# pcb.net
KiCad netlist of a schematic drawn in EAGLE
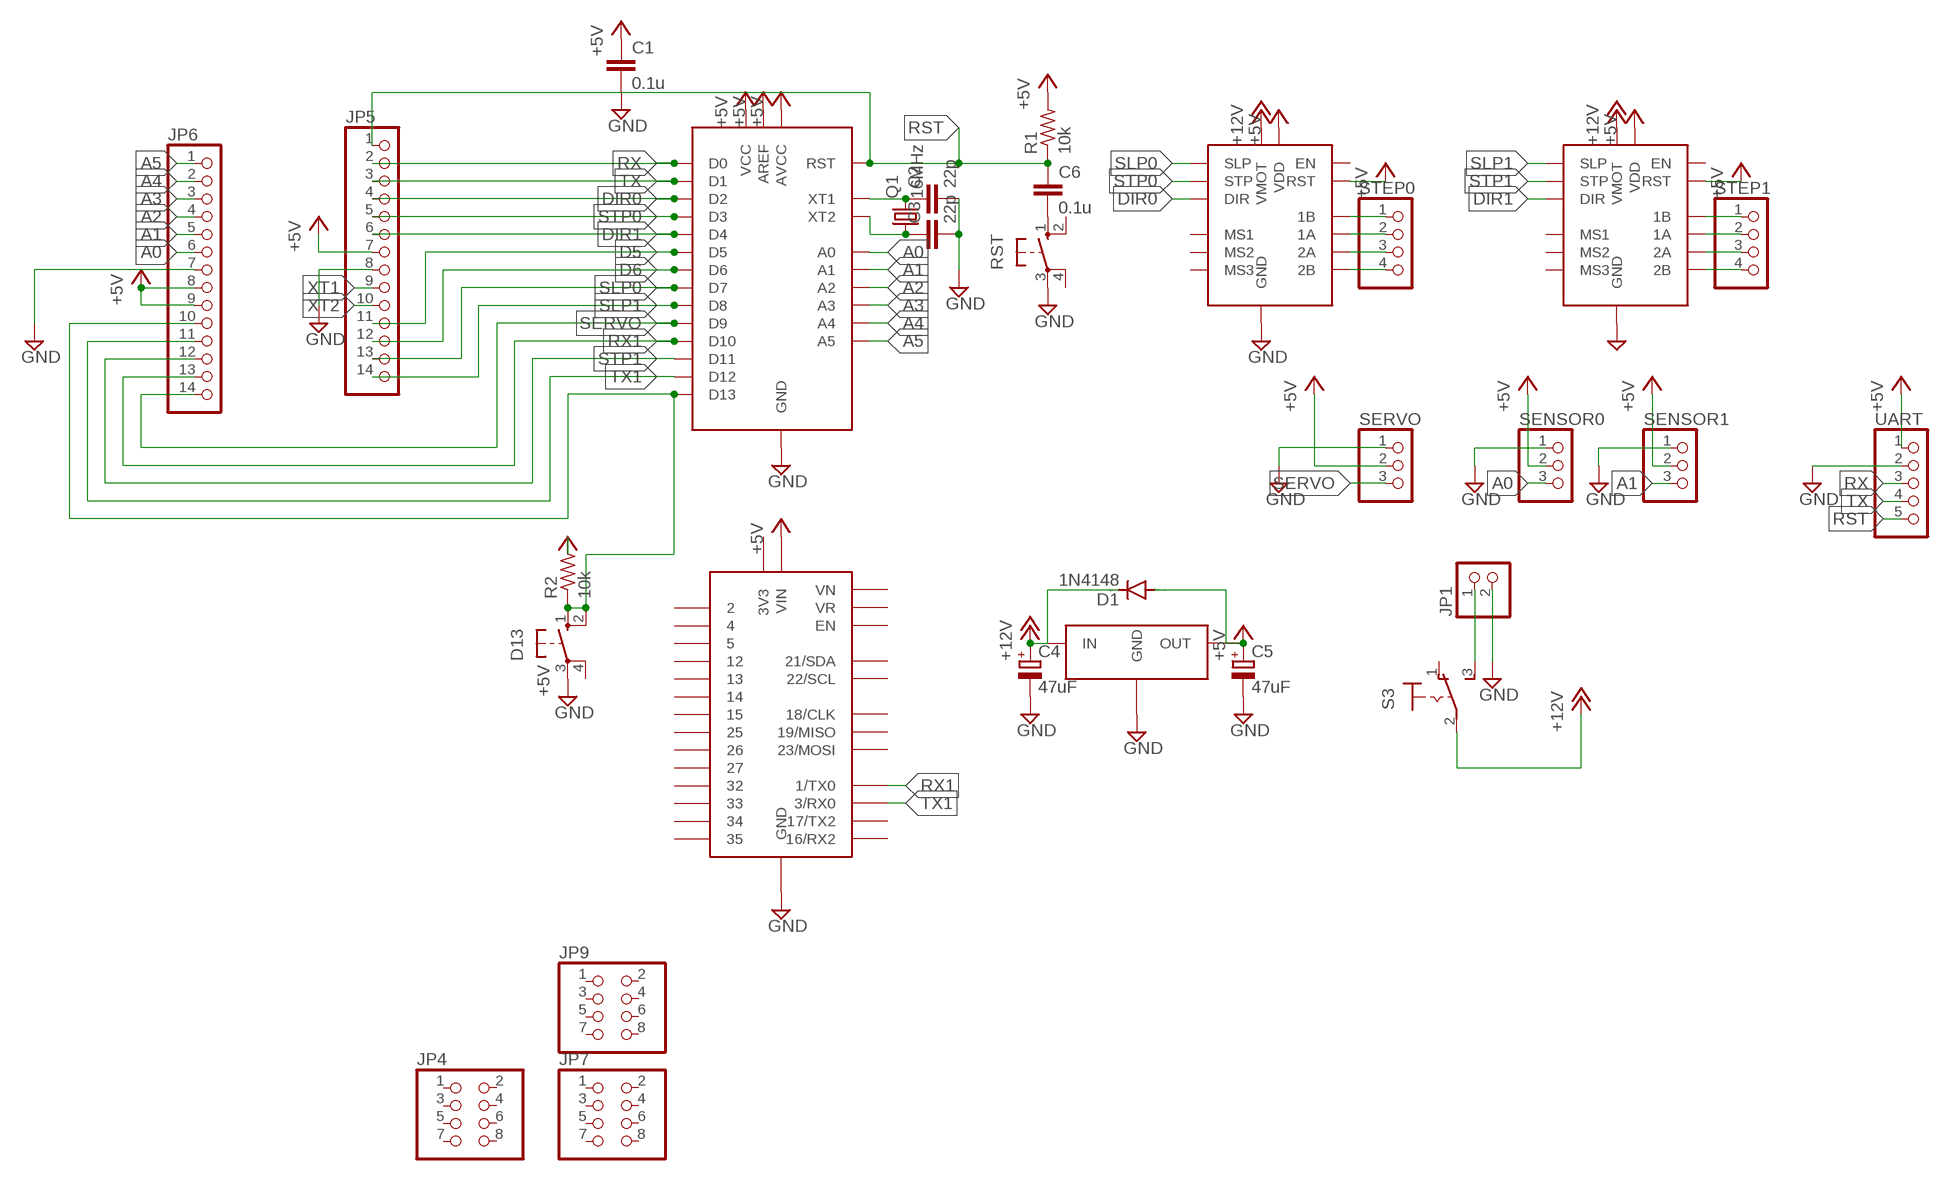
[diagram p0: schematic, sheet 1]

(export (version "E")
  (design (tool "Eeschema 10.0.6"))
  (components
    (comp (ref "C1")
      (value "0.1u")
      (footprint "eagle-import:C025-025X050")
      (libsource (lib "eagle-import") (part "C-EU025-025X050"))
    )
    (comp (ref "C2")
      (value "22p")
      (footprint "eagle-import:C025-025X050")
      (libsource (lib "eagle-import") (part "C-EU025-025X050"))
    )
    (comp (ref "C3")
      (value "22p")
      (footprint "eagle-import:C025-025X050")
      (libsource (lib "eagle-import") (part "C-EU025-025X050"))
    )
    (comp (ref "C4")
      (value "47uF")
      (footprint "eagle-import:E2,5-5")
      (libsource (lib "eagle-import") (part "CPOL-EUE2.5-5"))
    )
    (comp (ref "C5")
      (value "47uF")
      (footprint "eagle-import:E2,5-5")
      (libsource (lib "eagle-import") (part "CPOL-EUE2.5-5"))
    )
    (comp (ref "C6")
      (value "0.1u")
      (footprint "eagle-import:C025-025X050")
      (libsource (lib "eagle-import") (part "C-EU025-025X050"))
    )
    (comp (ref "D1")
      (value "1N4148")
      (footprint "eagle-import:DO35-7")
      (libsource (lib "eagle-import") (part "1N4148"))
    )
    (comp (ref "D13")
      (value "10-XX")
      (footprint "eagle-import:B3F-10XX")
      (fields (field (name "MPN") "B3F-1000"))
      (libsource (lib "eagle-import") (part "10-XX"))
    )
    (comp (ref "IC1")
      (value "ATMEGA328P-3")
      (footprint "eagle-import:DIL28-3")
      (libsource (lib "eagle-import") (part "ATMEGA328P-3"))
    )
    (comp (ref "JP1")
      (value "PINHD-1X2")
      (footprint "eagle-import:1X02")
      (libsource (lib "eagle-import") (part "PINHD-1X2"))
    )
    (comp (ref "JP4")
      (value "PINHD-2X4")
      (footprint "eagle-import:2X04")
      (libsource (lib "eagle-import") (part "PINHD-2X4"))
    )
    (comp (ref "JP5")
      (value "PINHD-1X14")
      (footprint "eagle-import:1X14")
      (libsource (lib "eagle-import") (part "PINHD-1X14"))
    )
    (comp (ref "JP6")
      (value "PINHD-1X14")
      (footprint "eagle-import:1X14")
      (libsource (lib "eagle-import") (part "PINHD-1X14"))
    )
    (comp (ref "JP7")
      (value "PINHD-2X4")
      (footprint "eagle-import:2X04")
      (libsource (lib "eagle-import") (part "PINHD-2X4"))
    )
    (comp (ref "JP9")
      (value "PINHD-2X4")
      (footprint "eagle-import:2X04")
      (libsource (lib "eagle-import") (part "PINHD-2X4"))
    )
    (comp (ref "Q1")
      (value "16MHz")
      (footprint "eagle-import:HC49_S")
      (libsource (lib "eagle-import") (part "CRYSTALHC49S"))
    )
    (comp (ref "R1")
      (value "10k")
      (footprint "eagle-import:0204_7")
      (libsource (lib "eagle-import") (part "R-US_0204/7"))
    )
    (comp (ref "R2")
      (value "10k")
      (footprint "eagle-import:0204_7")
      (libsource (lib "eagle-import") (part "R-US_0204/7"))
    )
    (comp (ref "RST")
      (value "10-XX")
      (footprint "eagle-import:B3F-10XX")
      (fields (field (name "MPN") "B3F-1000"))
      (libsource (lib "eagle-import") (part "10-XX"))
    )
    (comp (ref "S3")
      (value "TOGGLE")
      (footprint "eagle-import:TOGGLE")
      (libsource (lib "eagle-import") (part "TOGGLE"))
    )
    (comp (ref "SENSOR0")
      (value "PINHD-1X3")
      (footprint "eagle-import:1X03")
      (libsource (lib "eagle-import") (part "PINHD-1X3"))
    )
    (comp (ref "SENSOR1")
      (value "PINHD-1X3")
      (footprint "eagle-import:1X03")
      (libsource (lib "eagle-import") (part "PINHD-1X3"))
    )
    (comp (ref "SERVO")
      (value "PINHD-1X3")
      (footprint "eagle-import:1X03")
      (libsource (lib "eagle-import") (part "PINHD-1X3"))
    )
    (comp (ref "STEP0")
      (value "PINHD-1X4")
      (footprint "eagle-import:1X04")
      (libsource (lib "eagle-import") (part "PINHD-1X4"))
    )
    (comp (ref "STEP1")
      (value "PINHD-1X4")
      (footprint "eagle-import:1X04")
      (libsource (lib "eagle-import") (part "PINHD-1X4"))
    )
    (comp (ref "U$1")
      (value "A4988")
      (footprint "eagle-import:A4988")
      (libsource (lib "eagle-import") (part "A4988"))
    )
    (comp (ref "U$2")
      (value "A4988")
      (footprint "eagle-import:A4988")
      (libsource (lib "eagle-import") (part "A4988"))
    )
    (comp (ref "U$3")
      (value "NODE32S")
      (footprint "eagle-import:NODE32S")
      (libsource (lib "eagle-import") (part "NODE32S"))
    )
    (comp (ref "U$5")
      (value "NJM7805")
      (footprint "eagle-import:NJM7805")
      (libsource (lib "eagle-import") (part "NJM7805"))
    )
    (comp (ref "UART")
      (value "PINHD-1X5")
      (footprint "eagle-import:1X05")
      (libsource (lib "eagle-import") (part "PINHD-1X5"))
    )
  )
  (nets
    (net (code "1") (name "+5V") (class "Default")
      (node (ref "C1") (pin "1") (pinfunction "1_1") (pintype "passive"))
      (node (ref "C5") (pin "+") (pinfunction "+_+") (pintype "passive"))
      (node (ref "D1") (pin "A") (pinfunction "A_A") (pintype "passive"))
      (node (ref "IC1") (pin "AREF") (pinfunction "AREF_AREF") (pintype "bidirectional"))
      (node (ref "IC1") (pin "AVCC") (pinfunction "AVCC_AVCC") (pintype "bidirectional"))
      (node (ref "IC1") (pin "VCC") (pinfunction "VCC_VCC") (pintype "bidirectional"))
      (node (ref "JP5") (pin "7") (pinfunction "7_7") (pintype "passive"))
      (node (ref "JP6") (pin "8") (pinfunction "8_8") (pintype "passive"))
      (node (ref "JP6") (pin "9") (pinfunction "9_9") (pintype "passive"))
      (node (ref "R1") (pin "2") (pinfunction "2_2") (pintype "passive"))
      (node (ref "R2") (pin "2") (pinfunction "2_2") (pintype "passive"))
      (node (ref "SENSOR0") (pin "2") (pinfunction "2_2") (pintype "passive"))
      (node (ref "SENSOR1") (pin "2") (pinfunction "2_2") (pintype "passive"))
      (node (ref "SERVO") (pin "2") (pinfunction "2_2") (pintype "passive"))
      (node (ref "U$1") (pin "RST") (pinfunction "RST_RST") (pintype "bidirectional"))
      (node (ref "U$1") (pin "VDD") (pinfunction "VDD_VDD") (pintype "bidirectional"))
      (node (ref "U$2") (pin "RST") (pinfunction "RST_RST") (pintype "bidirectional"))
      (node (ref "U$2") (pin "VDD") (pinfunction "VDD_VDD") (pintype "bidirectional"))
      (node (ref "U$3") (pin "VIN") (pinfunction "VIN_VIN") (pintype "bidirectional"))
      (node (ref "U$5") (pin "OUT") (pinfunction "OUT_OUT") (pintype "bidirectional"))
      (node (ref "UART") (pin "1") (pinfunction "1_1") (pintype "passive"))
    )
    (net (code "2") (name "+12V") (class "Default")
      (node (ref "C4") (pin "+") (pinfunction "+_+") (pintype "passive"))
      (node (ref "D1") (pin "C") (pinfunction "C_C") (pintype "passive"))
      (node (ref "S3") (pin "2") (pinfunction "P_2") (pintype "passive"))
      (node (ref "U$1") (pin "VMOT") (pinfunction "VMOT_VMOT") (pintype "bidirectional"))
      (node (ref "U$2") (pin "VMOT") (pinfunction "VMOT_VMOT") (pintype "bidirectional"))
      (node (ref "U$5") (pin "IN") (pinfunction "IN_IN") (pintype "bidirectional"))
    )
    (net (code "3") (name "A0") (class "Default")
      (node (ref "IC1") (pin "A0") (pinfunction "A0_A0") (pintype "bidirectional"))
      (node (ref "JP6") (pin "6") (pinfunction "6_6") (pintype "passive"))
      (node (ref "SENSOR0") (pin "3") (pinfunction "3_3") (pintype "passive"))
    )
    (net (code "4") (name "A1") (class "Default")
      (node (ref "IC1") (pin "A1") (pinfunction "A1_A1") (pintype "bidirectional"))
      (node (ref "JP6") (pin "5") (pinfunction "5_5") (pintype "passive"))
      (node (ref "SENSOR1") (pin "3") (pinfunction "3_3") (pintype "passive"))
    )
    (net (code "5") (name "A2") (class "Default")
      (node (ref "IC1") (pin "A2") (pinfunction "A2_A2") (pintype "bidirectional"))
      (node (ref "JP6") (pin "4") (pinfunction "4_4") (pintype "passive"))
    )
    (net (code "6") (name "A3") (class "Default")
      (node (ref "IC1") (pin "A3") (pinfunction "A3_A3") (pintype "bidirectional"))
      (node (ref "JP6") (pin "3") (pinfunction "3_3") (pintype "passive"))
    )
    (net (code "7") (name "A4") (class "Default")
      (node (ref "IC1") (pin "A4") (pinfunction "A4_A4") (pintype "bidirectional"))
      (node (ref "JP6") (pin "2") (pinfunction "2_2") (pintype "passive"))
    )
    (net (code "8") (name "A5") (class "Default")
      (node (ref "IC1") (pin "A5") (pinfunction "A5_A5") (pintype "bidirectional"))
      (node (ref "JP6") (pin "1") (pinfunction "1_1") (pintype "passive"))
    )
    (net (code "9") (name "D5") (class "Default")
      (node (ref "IC1") (pin "D5") (pinfunction "D5_D5") (pintype "bidirectional"))
      (node (ref "JP5") (pin "11") (pinfunction "11_11") (pintype "passive"))
    )
    (net (code "10") (name "D6") (class "Default")
      (node (ref "IC1") (pin "D6") (pinfunction "D6_D6") (pintype "bidirectional"))
      (node (ref "JP5") (pin "12") (pinfunction "12_12") (pintype "passive"))
    )
    (net (code "11") (name "DIR0") (class "Default")
      (node (ref "IC1") (pin "D2") (pinfunction "D2_D2") (pintype "bidirectional"))
      (node (ref "JP5") (pin "4") (pinfunction "4_4") (pintype "passive"))
      (node (ref "U$1") (pin "DIR") (pinfunction "DIR_DIR") (pintype "bidirectional"))
    )
    (net (code "12") (name "DIR1") (class "Default")
      (node (ref "IC1") (pin "D4") (pinfunction "D4_D4") (pintype "bidirectional"))
      (node (ref "JP5") (pin "6") (pinfunction "6_6") (pintype "passive"))
      (node (ref "U$2") (pin "DIR") (pinfunction "DIR_DIR") (pintype "bidirectional"))
    )
    (net (code "13") (name "GND") (class "Default")
      (node (ref "C1") (pin "2") (pinfunction "2_2") (pintype "passive"))
      (node (ref "C2") (pin "2") (pinfunction "2_2") (pintype "passive"))
      (node (ref "C3") (pin "2") (pinfunction "2_2") (pintype "passive"))
      (node (ref "C4") (pin "-") (pinfunction "-_-") (pintype "passive"))
      (node (ref "C5") (pin "-") (pinfunction "-_-") (pintype "passive"))
      (node (ref "D13") (pin "3") (pinfunction "P_3") (pintype "passive"))
      (node (ref "IC1") (pin "GND1") (pinfunction "GND_GND1") (pintype "bidirectional"))
      (node (ref "IC1") (pin "GND2") (pinfunction "GND_GND2") (pintype "bidirectional"))
      (node (ref "JP1") (pin "2") (pinfunction "2_2") (pintype "passive"))
      (node (ref "JP5") (pin "8") (pinfunction "8_8") (pintype "passive"))
      (node (ref "JP6") (pin "7") (pinfunction "7_7") (pintype "passive"))
      (node (ref "RST") (pin "3") (pinfunction "P_3") (pintype "passive"))
      (node (ref "SENSOR0") (pin "1") (pinfunction "1_1") (pintype "passive"))
      (node (ref "SENSOR1") (pin "1") (pinfunction "1_1") (pintype "passive"))
      (node (ref "SERVO") (pin "1") (pinfunction "1_1") (pintype "passive"))
      (node (ref "U$1") (pin "GND0") (pinfunction "GND_GND0") (pintype "bidirectional"))
      (node (ref "U$1") (pin "GND1") (pinfunction "GND_GND1") (pintype "bidirectional"))
      (node (ref "U$2") (pin "GND0") (pinfunction "GND_GND0") (pintype "bidirectional"))
      (node (ref "U$2") (pin "GND1") (pinfunction "GND_GND1") (pintype "bidirectional"))
      (node (ref "U$3") (pin "GND") (pinfunction "GND_GND") (pintype "bidirectional"))
      (node (ref "U$3") (pin "GND1") (pinfunction "GND_GND1") (pintype "bidirectional"))
      (node (ref "U$5") (pin "GND") (pinfunction "GND_GND") (pintype "bidirectional"))
      (node (ref "UART") (pin "2") (pinfunction "2_2") (pintype "passive"))
    )
    (net (code "14") (name "Net-(D13-S)") (class "Default")
      (node (ref "D13") (pin "1") (pinfunction "S_1") (pintype "passive"))
      (node (ref "D13") (pin "2") (pinfunction "S1_2") (pintype "passive"))
      (node (ref "IC1") (pin "D13") (pinfunction "D13_D13") (pintype "bidirectional"))
      (node (ref "JP6") (pin "10") (pinfunction "10_10") (pintype "passive"))
      (node (ref "R2") (pin "1") (pinfunction "1_1") (pintype "passive"))
    )
    (net (code "15") (name "Net-(RST-S)") (class "Default")
      (node (ref "C6") (pin "2") (pinfunction "2_2") (pintype "passive"))
      (node (ref "RST") (pin "1") (pinfunction "S_1") (pintype "passive"))
    )
    (net (code "16") (name "Net-(S3-S)") (class "Default")
      (node (ref "JP1") (pin "1") (pinfunction "1_1") (pintype "passive"))
      (node (ref "S3") (pin "3") (pinfunction "S_3") (pintype "passive"))
    )
    (net (code "17") (name "Net-(STEP0-Pad1)") (class "Default")
      (node (ref "STEP0") (pin "1") (pinfunction "1_1") (pintype "passive"))
      (node (ref "U$1") (pin "1B") (pinfunction "1B_1B") (pintype "bidirectional"))
    )
    (net (code "18") (name "Net-(STEP0-Pad2)") (class "Default")
      (node (ref "STEP0") (pin "2") (pinfunction "2_2") (pintype "passive"))
      (node (ref "U$1") (pin "1A") (pinfunction "1A_1A") (pintype "bidirectional"))
    )
    (net (code "19") (name "Net-(STEP0-Pad3)") (class "Default")
      (node (ref "STEP0") (pin "3") (pinfunction "3_3") (pintype "passive"))
      (node (ref "U$1") (pin "2A") (pinfunction "2A_2A") (pintype "bidirectional"))
    )
    (net (code "20") (name "Net-(STEP0-Pad4)") (class "Default")
      (node (ref "STEP0") (pin "4") (pinfunction "4_4") (pintype "passive"))
      (node (ref "U$1") (pin "2B") (pinfunction "2B_2B") (pintype "bidirectional"))
    )
    (net (code "21") (name "Net-(STEP1-Pad1)") (class "Default")
      (node (ref "STEP1") (pin "1") (pinfunction "1_1") (pintype "passive"))
      (node (ref "U$2") (pin "1B") (pinfunction "1B_1B") (pintype "bidirectional"))
    )
    (net (code "22") (name "Net-(STEP1-Pad2)") (class "Default")
      (node (ref "STEP1") (pin "2") (pinfunction "2_2") (pintype "passive"))
      (node (ref "U$2") (pin "1A") (pinfunction "1A_1A") (pintype "bidirectional"))
    )
    (net (code "23") (name "Net-(STEP1-Pad3)") (class "Default")
      (node (ref "STEP1") (pin "3") (pinfunction "3_3") (pintype "passive"))
      (node (ref "U$2") (pin "2A") (pinfunction "2A_2A") (pintype "bidirectional"))
    )
    (net (code "24") (name "Net-(STEP1-Pad4)") (class "Default")
      (node (ref "STEP1") (pin "4") (pinfunction "4_4") (pintype "passive"))
      (node (ref "U$2") (pin "2B") (pinfunction "2B_2B") (pintype "bidirectional"))
    )
    (net (code "25") (name "RST") (class "Default")
      (node (ref "C6") (pin "1") (pinfunction "1_1") (pintype "passive"))
      (node (ref "IC1") (pin "RST") (pinfunction "RST_RST") (pintype "bidirectional"))
      (node (ref "JP5") (pin "1") (pinfunction "1_1") (pintype "passive"))
      (node (ref "R1") (pin "1") (pinfunction "1_1") (pintype "passive"))
      (node (ref "UART") (pin "5") (pinfunction "5_5") (pintype "passive"))
    )
    (net (code "26") (name "RX") (class "Default")
      (node (ref "IC1") (pin "D0") (pinfunction "D0_D0") (pintype "bidirectional"))
      (node (ref "JP5") (pin "2") (pinfunction "2_2") (pintype "passive"))
      (node (ref "UART") (pin "3") (pinfunction "3_3") (pintype "passive"))
    )
    (net (code "27") (name "RX1") (class "Default")
      (node (ref "IC1") (pin "D10") (pinfunction "D10_D10") (pintype "bidirectional"))
      (node (ref "JP6") (pin "13") (pinfunction "13_13") (pintype "passive"))
      (node (ref "U$3") (pin "TX0") (pinfunction "1/TX0_TX0") (pintype "bidirectional"))
    )
    (net (code "28") (name "SERVO") (class "Default")
      (node (ref "IC1") (pin "D9") (pinfunction "D9_D9") (pintype "bidirectional"))
      (node (ref "JP6") (pin "14") (pinfunction "14_14") (pintype "passive"))
      (node (ref "SERVO") (pin "3") (pinfunction "3_3") (pintype "passive"))
    )
    (net (code "29") (name "SLP0") (class "Default")
      (node (ref "IC1") (pin "D7") (pinfunction "D7_D7") (pintype "bidirectional"))
      (node (ref "JP5") (pin "13") (pinfunction "13_13") (pintype "passive"))
      (node (ref "U$1") (pin "SLP") (pinfunction "SLP_SLP") (pintype "bidirectional"))
    )
    (net (code "30") (name "SLP1") (class "Default")
      (node (ref "IC1") (pin "D8") (pinfunction "D8_D8") (pintype "bidirectional"))
      (node (ref "JP5") (pin "14") (pinfunction "14_14") (pintype "passive"))
      (node (ref "U$2") (pin "SLP") (pinfunction "SLP_SLP") (pintype "bidirectional"))
    )
    (net (code "31") (name "STP0") (class "Default")
      (node (ref "IC1") (pin "D3") (pinfunction "D3_D3") (pintype "bidirectional"))
      (node (ref "JP5") (pin "5") (pinfunction "5_5") (pintype "passive"))
      (node (ref "U$1") (pin "STP") (pinfunction "STP_STP") (pintype "bidirectional"))
    )
    (net (code "32") (name "STP1") (class "Default")
      (node (ref "IC1") (pin "D11") (pinfunction "D11_D11") (pintype "bidirectional"))
      (node (ref "JP6") (pin "12") (pinfunction "12_12") (pintype "passive"))
      (node (ref "U$2") (pin "STP") (pinfunction "STP_STP") (pintype "bidirectional"))
    )
    (net (code "33") (name "TX") (class "Default")
      (node (ref "IC1") (pin "D1") (pinfunction "D1_D1") (pintype "bidirectional"))
      (node (ref "JP5") (pin "3") (pinfunction "3_3") (pintype "passive"))
      (node (ref "UART") (pin "4") (pinfunction "4_4") (pintype "passive"))
    )
    (net (code "34") (name "TX1") (class "Default")
      (node (ref "IC1") (pin "D12") (pinfunction "D12_D12") (pintype "bidirectional"))
      (node (ref "JP6") (pin "11") (pinfunction "11_11") (pintype "passive"))
      (node (ref "U$3") (pin "RX0") (pinfunction "3/RX0_RX0") (pintype "bidirectional"))
    )
    (net (code "35") (name "XT1") (class "Default")
      (node (ref "C2") (pin "1") (pinfunction "1_1") (pintype "passive"))
      (node (ref "IC1") (pin "XT1") (pinfunction "XT1_XT1") (pintype "bidirectional"))
      (node (ref "JP5") (pin "9") (pinfunction "9_9") (pintype "passive"))
      (node (ref "Q1") (pin "2") (pinfunction "2_2") (pintype "passive"))
    )
    (net (code "36") (name "XT2") (class "Default")
      (node (ref "C3") (pin "1") (pinfunction "1_1") (pintype "passive"))
      (node (ref "IC1") (pin "XT2") (pinfunction "XT2_XT2") (pintype "bidirectional"))
      (node (ref "JP5") (pin "10") (pinfunction "10_10") (pintype "passive"))
      (node (ref "Q1") (pin "1") (pinfunction "1_1") (pintype "passive"))
    )
    (net (code "37") (name "unconnected-(D13-P1-Pad4)") (class "Default")
      (node (ref "D13") (pin "4") (pinfunction "P1_4") (pintype "passive"))
    )
    (net (code "38") (name "unconnected-(JP4-Pad1)") (class "Default")
      (node (ref "JP4") (pin "1") (pinfunction "1_1") (pintype "passive"))
    )
    (net (code "39") (name "unconnected-(JP4-Pad2)") (class "Default")
      (node (ref "JP4") (pin "2") (pinfunction "2_2") (pintype "passive"))
    )
    (net (code "40") (name "unconnected-(JP4-Pad3)") (class "Default")
      (node (ref "JP4") (pin "3") (pinfunction "3_3") (pintype "passive"))
    )
    (net (code "41") (name "unconnected-(JP4-Pad4)") (class "Default")
      (node (ref "JP4") (pin "4") (pinfunction "4_4") (pintype "passive"))
    )
    (net (code "42") (name "unconnected-(JP4-Pad5)") (class "Default")
      (node (ref "JP4") (pin "5") (pinfunction "5_5") (pintype "passive"))
    )
    (net (code "43") (name "unconnected-(JP4-Pad6)") (class "Default")
      (node (ref "JP4") (pin "6") (pinfunction "6_6") (pintype "passive"))
    )
    (net (code "44") (name "unconnected-(JP4-Pad7)") (class "Default")
      (node (ref "JP4") (pin "7") (pinfunction "7_7") (pintype "passive"))
    )
    (net (code "45") (name "unconnected-(JP4-Pad8)") (class "Default")
      (node (ref "JP4") (pin "8") (pinfunction "8_8") (pintype "passive"))
    )
    (net (code "46") (name "unconnected-(JP7-Pad1)") (class "Default")
      (node (ref "JP7") (pin "1") (pinfunction "1_1") (pintype "passive"))
    )
    (net (code "47") (name "unconnected-(JP7-Pad2)") (class "Default")
      (node (ref "JP7") (pin "2") (pinfunction "2_2") (pintype "passive"))
    )
    (net (code "48") (name "unconnected-(JP7-Pad3)") (class "Default")
      (node (ref "JP7") (pin "3") (pinfunction "3_3") (pintype "passive"))
    )
    (net (code "49") (name "unconnected-(JP7-Pad4)") (class "Default")
      (node (ref "JP7") (pin "4") (pinfunction "4_4") (pintype "passive"))
    )
    (net (code "50") (name "unconnected-(JP7-Pad5)") (class "Default")
      (node (ref "JP7") (pin "5") (pinfunction "5_5") (pintype "passive"))
    )
    (net (code "51") (name "unconnected-(JP7-Pad6)") (class "Default")
      (node (ref "JP7") (pin "6") (pinfunction "6_6") (pintype "passive"))
    )
    (net (code "52") (name "unconnected-(JP7-Pad7)") (class "Default")
      (node (ref "JP7") (pin "7") (pinfunction "7_7") (pintype "passive"))
    )
    (net (code "53") (name "unconnected-(JP7-Pad8)") (class "Default")
      (node (ref "JP7") (pin "8") (pinfunction "8_8") (pintype "passive"))
    )
    (net (code "54") (name "unconnected-(JP9-Pad1)") (class "Default")
      (node (ref "JP9") (pin "1") (pinfunction "1_1") (pintype "passive"))
    )
    (net (code "55") (name "unconnected-(JP9-Pad2)") (class "Default")
      (node (ref "JP9") (pin "2") (pinfunction "2_2") (pintype "passive"))
    )
    (net (code "56") (name "unconnected-(JP9-Pad3)") (class "Default")
      (node (ref "JP9") (pin "3") (pinfunction "3_3") (pintype "passive"))
    )
    (net (code "57") (name "unconnected-(JP9-Pad4)") (class "Default")
      (node (ref "JP9") (pin "4") (pinfunction "4_4") (pintype "passive"))
    )
    (net (code "58") (name "unconnected-(JP9-Pad5)") (class "Default")
      (node (ref "JP9") (pin "5") (pinfunction "5_5") (pintype "passive"))
    )
    (net (code "59") (name "unconnected-(JP9-Pad6)") (class "Default")
      (node (ref "JP9") (pin "6") (pinfunction "6_6") (pintype "passive"))
    )
    (net (code "60") (name "unconnected-(JP9-Pad7)") (class "Default")
      (node (ref "JP9") (pin "7") (pinfunction "7_7") (pintype "passive"))
    )
    (net (code "61") (name "unconnected-(JP9-Pad8)") (class "Default")
      (node (ref "JP9") (pin "8") (pinfunction "8_8") (pintype "passive"))
    )
    (net (code "62") (name "unconnected-(RST-P1-Pad4)") (class "Default")
      (node (ref "RST") (pin "4") (pinfunction "P1_4") (pintype "passive"))
    )
    (net (code "63") (name "unconnected-(RST-S1-Pad2)") (class "Default")
      (node (ref "RST") (pin "2") (pinfunction "S1_2") (pintype "passive"))
    )
    (net (code "64") (name "unconnected-(S3-O-Pad1)") (class "Default")
      (node (ref "S3") (pin "1") (pinfunction "O_1") (pintype "passive"))
    )
    (net (code "65") (name "unconnected-(U$1-PadEN)") (class "Default")
      (node (ref "U$1") (pin "EN") (pinfunction "EN_EN") (pintype "bidirectional"))
    )
    (net (code "66") (name "unconnected-(U$1-PadMS1)") (class "Default")
      (node (ref "U$1") (pin "MS1") (pinfunction "MS1_MS1") (pintype "bidirectional"))
    )
    (net (code "67") (name "unconnected-(U$1-PadMS2)") (class "Default")
      (node (ref "U$1") (pin "MS2") (pinfunction "MS2_MS2") (pintype "bidirectional"))
    )
    (net (code "68") (name "unconnected-(U$1-PadMS3)") (class "Default")
      (node (ref "U$1") (pin "MS3") (pinfunction "MS3_MS3") (pintype "bidirectional"))
    )
    (net (code "69") (name "unconnected-(U$2-PadEN)") (class "Default")
      (node (ref "U$2") (pin "EN") (pinfunction "EN_EN") (pintype "bidirectional"))
    )
    (net (code "70") (name "unconnected-(U$2-PadMS1)") (class "Default")
      (node (ref "U$2") (pin "MS1") (pinfunction "MS1_MS1") (pintype "bidirectional"))
    )
    (net (code "71") (name "unconnected-(U$2-PadMS2)") (class "Default")
      (node (ref "U$2") (pin "MS2") (pinfunction "MS2_MS2") (pintype "bidirectional"))
    )
    (net (code "72") (name "unconnected-(U$2-PadMS3)") (class "Default")
      (node (ref "U$2") (pin "MS3") (pinfunction "MS3_MS3") (pintype "bidirectional"))
    )
    (net (code "73") (name "unconnected-(U$3-16{slash}RX2-PadRX2)") (class "Default")
      (node (ref "U$3") (pin "RX2") (pinfunction "16/RX2_RX2") (pintype "bidirectional"))
    )
    (net (code "74") (name "unconnected-(U$3-17{slash}TX2-PadTX2)") (class "Default")
      (node (ref "U$3") (pin "TX2") (pinfunction "17/TX2_TX2") (pintype "bidirectional"))
    )
    (net (code "75") (name "unconnected-(U$3-18{slash}CLK-Pad18)") (class "Default")
      (node (ref "U$3") (pin "18") (pinfunction "18/CLK_18") (pintype "bidirectional"))
    )
    (net (code "76") (name "unconnected-(U$3-19{slash}MISO-Pad19)") (class "Default")
      (node (ref "U$3") (pin "19") (pinfunction "19/MISO_19") (pintype "bidirectional"))
    )
    (net (code "77") (name "unconnected-(U$3-21{slash}SDA-Pad21)") (class "Default")
      (node (ref "U$3") (pin "21") (pinfunction "21/SDA_21") (pintype "bidirectional"))
    )
    (net (code "78") (name "unconnected-(U$3-22{slash}SCL-PadD22)") (class "Default")
      (node (ref "U$3") (pin "D22") (pinfunction "22/SCL_D22") (pintype "bidirectional"))
    )
    (net (code "79") (name "unconnected-(U$3-23{slash}MOSI-PadD23)") (class "Default")
      (node (ref "U$3") (pin "D23") (pinfunction "23/MOSI_D23") (pintype "bidirectional"))
    )
    (net (code "80") (name "unconnected-(U$3-Pad2)") (class "Default")
      (node (ref "U$3") (pin "2") (pinfunction "2_2") (pintype "bidirectional"))
    )
    (net (code "81") (name "unconnected-(U$3-Pad3V3)") (class "Default")
      (node (ref "U$3") (pin "3V3") (pinfunction "3V3_3V3") (pintype "bidirectional"))
    )
    (net (code "82") (name "unconnected-(U$3-Pad4)") (class "Default")
      (node (ref "U$3") (pin "4") (pinfunction "4_4") (pintype "bidirectional"))
    )
    (net (code "83") (name "unconnected-(U$3-Pad5)") (class "Default")
      (node (ref "U$3") (pin "5") (pinfunction "5_5") (pintype "bidirectional"))
    )
    (net (code "84") (name "unconnected-(U$3-Pad12)") (class "Default")
      (node (ref "U$3") (pin "12") (pinfunction "12_12") (pintype "bidirectional"))
    )
    (net (code "85") (name "unconnected-(U$3-Pad13)") (class "Default")
      (node (ref "U$3") (pin "13") (pinfunction "13_13") (pintype "bidirectional"))
    )
    (net (code "86") (name "unconnected-(U$3-Pad14)") (class "Default")
      (node (ref "U$3") (pin "14") (pinfunction "14_14") (pintype "bidirectional"))
    )
    (net (code "87") (name "unconnected-(U$3-Pad15)") (class "Default")
      (node (ref "U$3") (pin "15") (pinfunction "15_15") (pintype "bidirectional"))
    )
    (net (code "88") (name "unconnected-(U$3-Pad25)") (class "Default")
      (node (ref "U$3") (pin "25") (pinfunction "25_25") (pintype "bidirectional"))
    )
    (net (code "89") (name "unconnected-(U$3-Pad26)") (class "Default")
      (node (ref "U$3") (pin "26") (pinfunction "26_26") (pintype "bidirectional"))
    )
    (net (code "90") (name "unconnected-(U$3-Pad27)") (class "Default")
      (node (ref "U$3") (pin "27") (pinfunction "27_27") (pintype "bidirectional"))
    )
    (net (code "91") (name "unconnected-(U$3-Pad32)") (class "Default")
      (node (ref "U$3") (pin "32") (pinfunction "32_32") (pintype "bidirectional"))
    )
    (net (code "92") (name "unconnected-(U$3-Pad33)") (class "Default")
      (node (ref "U$3") (pin "33") (pinfunction "33_33") (pintype "bidirectional"))
    )
    (net (code "93") (name "unconnected-(U$3-Pad34)") (class "Default")
      (node (ref "U$3") (pin "34") (pinfunction "34_34") (pintype "bidirectional"))
    )
    (net (code "94") (name "unconnected-(U$3-Pad35)") (class "Default")
      (node (ref "U$3") (pin "35") (pinfunction "35_35") (pintype "bidirectional"))
    )
    (net (code "95") (name "unconnected-(U$3-PadEN)") (class "Default")
      (node (ref "U$3") (pin "EN") (pinfunction "EN_EN") (pintype "bidirectional"))
    )
    (net (code "96") (name "unconnected-(U$3-PadVN)") (class "Default")
      (node (ref "U$3") (pin "VN") (pinfunction "VN_VN") (pintype "bidirectional"))
    )
    (net (code "97") (name "unconnected-(U$3-PadVR)") (class "Default")
      (node (ref "U$3") (pin "VR") (pinfunction "VR_VR") (pintype "bidirectional"))
    )
  )
)
